# RyanTest1.net
KiCad netlist of a schematic drawn in EAGLE
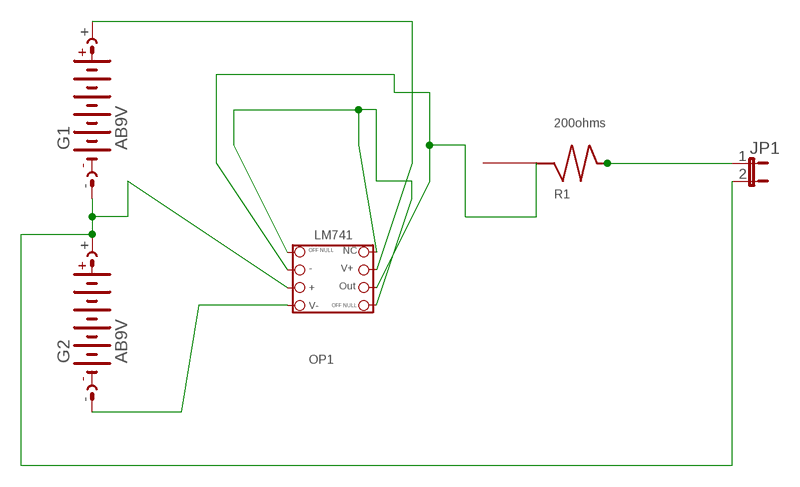
[diagram p0: schematic, sheet 1]

(export (version "E")
  (design (tool "Eeschema 10.0.6"))
  (components
    (comp (ref "G1")
      (value "AB9V")
      (footprint "eagle-import:AB9V")
      (libsource (lib "eagle-import") (part "AB9V"))
    )
    (comp (ref "G2")
      (value "AB9V")
      (footprint "eagle-import:AB9V")
      (libsource (lib "eagle-import") (part "AB9V"))
    )
    (comp (ref "JP1")
      (value "JP1E")
      (footprint "eagle-import:JP1")
      (libsource (lib "eagle-import") (part "JP1E"))
    )
    (comp (ref "OP1")
      (value "OPAMP1")
      (footprint "eagle-import:OPAMP1")
      (libsource (lib "eagle-import") (part "OPAMP1"))
    )
    (comp (ref "R1")
      (value "200ohms")
      (footprint "eagle-import:R-10")
      (libsource (lib "eagle-import") (part "R-10"))
    )
  )
  (nets
    (net (code "1") (name "Net-(OP1-P$1)") (class "Default")
      (node (ref "OP1") (pin "1") (pinfunction "P$1_1") (pintype "bidirectional"))
      (node (ref "OP1") (pin "5") (pinfunction "P$5_5") (pintype "bidirectional"))
      (node (ref "OP1") (pin "8") (pinfunction "P$8_8") (pintype "bidirectional"))
    )
    (net (code "2") (name "Net-(OP1-P$2)") (class "Default")
      (node (ref "OP1") (pin "2") (pinfunction "P$2_2") (pintype "bidirectional"))
      (node (ref "OP1") (pin "7") (pinfunction "P$7_7") (pintype "bidirectional"))
      (node (ref "R1") (pin "3") (pinfunction "1_3") (pintype "bidirectional"))
    )
    (net (code "3") (name "Net-(OP1-P$3)") (class "Default")
      (node (ref "G1") (pin "-") (pinfunction "-_-") (pintype "passive"))
      (node (ref "G2") (pin "+") (pinfunction "+_+") (pintype "passive"))
      (node (ref "JP1") (pin "2") (pinfunction "2_2") (pintype "passive"))
      (node (ref "OP1") (pin "3") (pinfunction "P$3_3") (pintype "bidirectional"))
    )
    (net (code "4") (name "Net-(OP1-P$4)") (class "Default")
      (node (ref "G2") (pin "-") (pinfunction "-_-") (pintype "passive"))
      (node (ref "OP1") (pin "4") (pinfunction "P$4_4") (pintype "bidirectional"))
    )
    (net (code "5") (name "Net-(OP1-P$6)") (class "Default")
      (node (ref "G1") (pin "+") (pinfunction "+_+") (pintype "passive"))
      (node (ref "OP1") (pin "6") (pinfunction "P$6_6") (pintype "bidirectional"))
    )
    (net (code "6") (name "Net-(R1-2)") (class "Default")
      (node (ref "JP1") (pin "1") (pinfunction "1_1") (pintype "passive"))
      (node (ref "R1") (pin "4") (pinfunction "2_4") (pintype "bidirectional"))
    )
  )
)
